# design.net
KiCad netlist of a schematic drawn in Altium Designer
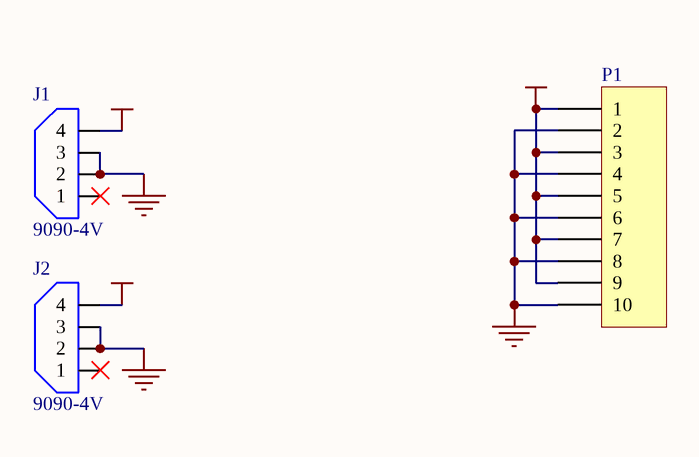
[diagram p0: 電源分接.SchDoc]

(export (version "E")
  (design (tool "Eeschema 10.0.6"))
  (components
    (comp (ref "J1") (value "9090-4V") (footprint "9090-4V") (libsource (lib "mydata") (part "9090-4V")))
    (comp (ref "J2") (value "9090-4V") (footprint "9090-4V") (libsource (lib "mydata") (part "9090-4V")))
    (comp (ref "P1")
      (value "Header 10")
      (footprint "10pin 3.96mm")
      (description "Header, 10-Pin")
      (fields (field (name "PUBLISHER") "Altium Limited"))
      (libsource (lib "Miscellaneous Connectors") (part "Header 10"))
    )
  )
  (nets
    (net (code "1") (name "+12") (class "Default")
      (node (ref "J1") (pin "4") (pinfunction "4_4") (pintype "passive"))
      (node (ref "J2") (pin "4") (pinfunction "4_4") (pintype "passive"))
      (node (ref "P1") (pin "1") (pinfunction "1_1") (pintype "passive"))
      (node (ref "P1") (pin "3") (pinfunction "3_3") (pintype "passive"))
      (node (ref "P1") (pin "5") (pinfunction "5_5") (pintype "passive"))
      (node (ref "P1") (pin "7") (pinfunction "7_7") (pintype "passive"))
      (node (ref "P1") (pin "9") (pinfunction "9_9") (pintype "passive"))
    )
    (net (code "2") (name "GND") (class "Default")
      (node (ref "J1") (pin "2") (pinfunction "2_2") (pintype "passive"))
      (node (ref "J1") (pin "3") (pinfunction "3_3") (pintype "passive"))
      (node (ref "J2") (pin "2") (pinfunction "2_2") (pintype "passive"))
      (node (ref "J2") (pin "3") (pinfunction "3_3") (pintype "passive"))
      (node (ref "P1") (pin "10") (pinfunction "10_10") (pintype "passive"))
      (node (ref "P1") (pin "2") (pinfunction "2_2") (pintype "passive"))
      (node (ref "P1") (pin "4") (pinfunction "4_4") (pintype "passive"))
      (node (ref "P1") (pin "6") (pinfunction "6_6") (pintype "passive"))
      (node (ref "P1") (pin "8") (pinfunction "8_8") (pintype "passive"))
    )
    (net (code "3") (name "unconnected-(J1-Pad1)") (class "Default")
      (node (ref "J1") (pin "1") (pinfunction "1_1") (pintype "passive+no_connect"))
    )
    (net (code "4") (name "unconnected-(J2-Pad1)") (class "Default")
      (node (ref "J2") (pin "1") (pinfunction "1_1") (pintype "passive+no_connect"))
    )
  )
)
